# Steering_Wheel_Board.net
KiCad netlist of a schematic drawn in EAGLE
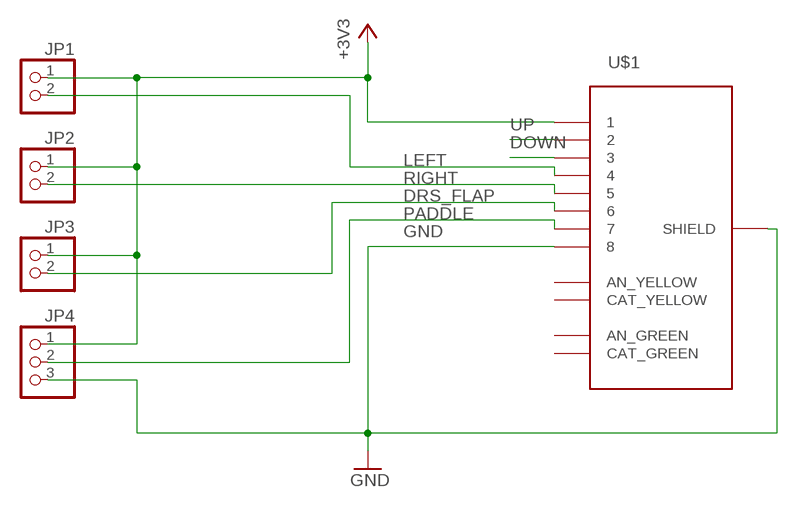
[diagram p0: schematic, sheet 1]

(export (version "E")
  (design (tool "Eeschema 10.0.6"))
  (components
    (comp (ref "JP1")
      (value "PINHD-1X2")
      (footprint "eagle-import:1X02")
      (libsource (lib "eagle-import") (part "PINHD-1X2"))
    )
    (comp (ref "JP2")
      (value "PINHD-1X2")
      (footprint "eagle-import:1X02")
      (libsource (lib "eagle-import") (part "PINHD-1X2"))
    )
    (comp (ref "JP3")
      (value "PINHD-1X2")
      (footprint "eagle-import:1X02")
      (libsource (lib "eagle-import") (part "PINHD-1X2"))
    )
    (comp (ref "JP4")
      (value "PINHD-1X3")
      (footprint "eagle-import:1X03")
      (libsource (lib "eagle-import") (part "PINHD-1X3"))
    )
    (comp (ref "U$1")
      (value "RJ-45_12-PIN")
      (footprint "eagle-import:RJ-45")
      (libsource (lib "eagle-import") (part "RJ-45_12-PIN"))
    )
  )
  (nets
    (net (code "1") (name "+3V3") (class "Default")
      (node (ref "JP1") (pin "1") (pinfunction "1_1") (pintype "passive"))
      (node (ref "JP2") (pin "1") (pinfunction "1_1") (pintype "passive"))
      (node (ref "JP3") (pin "1") (pinfunction "1_1") (pintype "passive"))
      (node (ref "JP4") (pin "1") (pinfunction "1_1") (pintype "passive"))
      (node (ref "U$1") (pin "P$1") (pinfunction "1_P$1") (pintype "bidirectional"))
    )
    (net (code "2") (name "/DOWN") (class "Default")
      (node (ref "U$1") (pin "P$3") (pinfunction "3_P$3") (pintype "bidirectional"))
    )
    (net (code "3") (name "/DRS_FLAP") (class "Default")
      (node (ref "JP3") (pin "2") (pinfunction "2_2") (pintype "passive"))
      (node (ref "U$1") (pin "P$6") (pinfunction "6_P$6") (pintype "bidirectional"))
    )
    (net (code "4") (name "/LEFT") (class "Default")
      (node (ref "JP1") (pin "2") (pinfunction "2_2") (pintype "passive"))
      (node (ref "U$1") (pin "P$4") (pinfunction "4_P$4") (pintype "bidirectional"))
    )
    (net (code "5") (name "/PADDLE") (class "Default")
      (node (ref "JP4") (pin "2") (pinfunction "2_2") (pintype "passive"))
      (node (ref "U$1") (pin "P$7") (pinfunction "7_P$7") (pintype "bidirectional"))
    )
    (net (code "6") (name "/RIGHT") (class "Default")
      (node (ref "JP2") (pin "2") (pinfunction "2_2") (pintype "passive"))
      (node (ref "U$1") (pin "P$5") (pinfunction "5_P$5") (pintype "bidirectional"))
    )
    (net (code "7") (name "/UP") (class "Default")
      (node (ref "U$1") (pin "P$2") (pinfunction "2_P$2") (pintype "bidirectional"))
    )
    (net (code "8") (name "GND") (class "Default")
      (node (ref "JP4") (pin "3") (pinfunction "3_3") (pintype "passive"))
      (node (ref "U$1") (pin "P$13") (pinfunction "SHIELD_P$13") (pintype "bidirectional"))
      (node (ref "U$1") (pin "P$8") (pinfunction "8_P$8") (pintype "bidirectional"))
    )
    (net (code "9") (name "unconnected-(U$1-AN_GREEN-PadP$11)") (class "Default")
      (node (ref "U$1") (pin "P$11") (pinfunction "AN_GREEN_P$11") (pintype "bidirectional"))
    )
    (net (code "10") (name "unconnected-(U$1-AN_YELLOW-PadP$9)") (class "Default")
      (node (ref "U$1") (pin "P$9") (pinfunction "AN_YELLOW_P$9") (pintype "bidirectional"))
    )
    (net (code "11") (name "unconnected-(U$1-CAT_GREEN-PadP$12)") (class "Default")
      (node (ref "U$1") (pin "P$12") (pinfunction "CAT_GREEN_P$12") (pintype "bidirectional"))
    )
    (net (code "12") (name "unconnected-(U$1-CAT_YELLOW-PadP$10)") (class "Default")
      (node (ref "U$1") (pin "P$10") (pinfunction "CAT_YELLOW_P$10") (pintype "bidirectional"))
    )
  )
)
